# power.net
KiCad netlist of a schematic drawn in Altium Designer
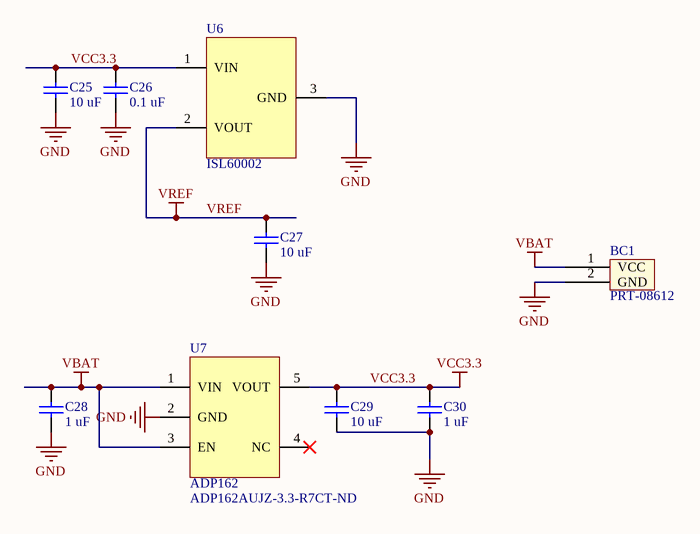
[diagram p0: power.SchDoc]

(export (version "E")
  (design (tool "Eeschema 10.0.6"))
  (components
    (comp (ref "BC1")
      (value "PRT-08612")
      (footprint "JST PH 2PIN")
      (description "2-pin JST-PH 2mm Battery Connector")
      (libsource (lib "opo_general") (part "JST-PH-2mm-2Pin"))
    )
    (comp (ref "C25")
      (value "10 uF")
      (footprint "0603")
      (description "Ceramic capacitor, 10 uF, 0603 package")
      (fields (field (name "TOLERANCE") "20%") (field (name "Comment") "Ceramic capacitor"))
      (libsource (lib "rlc") (part "C_10u_0603_ceramic"))
    )
    (comp (ref "C26")
      (value "0.1 uF")
      (footprint "0402")
      (description "Ceramic capacitor, 0.1u, 0402 package")
      (fields (field (name "TOLERANCE") "10%") (field (name "Comment") "Ceramic capacitor"))
      (libsource (lib "rlc") (part "C_0.1u_0402_ceramic"))
    )
    (comp (ref "C27")
      (value "10 uF")
      (footprint "0603")
      (description "Ceramic capacitor, 10 uF, 0603 package")
      (fields (field (name "TOLERANCE") "20%") (field (name "Comment") "Ceramic capacitor"))
      (libsource (lib "rlc") (part "C_10u_0603_ceramic"))
    )
    (comp (ref "C28")
      (value "1 uF")
      (footprint "0402")
      (description "Ceramic capacitor, 1 uF, 0402 package")
      (fields (field (name "TOLERANCE") "10%") (field (name "Comment") "Ceramic capacitor"))
      (libsource (lib "rlc") (part "C_1u_0402_ceramic"))
    )
    (comp (ref "C29")
      (value "10 uF")
      (footprint "0603")
      (description "Ceramic capacitor, 10 uF, 0603 package")
      (fields (field (name "TOLERANCE") "20%") (field (name "Comment") "Ceramic capacitor"))
      (libsource (lib "rlc") (part "C_10u_0603_ceramic"))
    )
    (comp (ref "C30")
      (value "1 uF")
      (footprint "0402")
      (description "Ceramic capacitor, 1 uF, 0402 package")
      (fields (field (name "TOLERANCE") "10%") (field (name "Comment") "Ceramic capacitor"))
      (libsource (lib "rlc") (part "C_1u_0402_ceramic"))
    )
    (comp (ref "U6")
      (value "ISL60002")
      (footprint "SOT23-3N")
      (description "IC VREF SERIES PREC SOT-23-3")
      (libsource (lib "opo") (part "ISL60002"))
    )
    (comp (ref "U7")
      (value "ADP162")
      (footprint "TSOT23-5")
      (description "Ultralow Quiescent Current,  150 mA, CMOS Linear Regulators")
      (fields (field (name "SUPPLIER PART NUMBER 1") "ADP162AUJZ-3.3-R7CT-ND"))
      (libsource (lib "opo") (part "ADP162"))
    )
  )
  (nets
    (net (code "1") (name "GND") (class "Default")
      (node (ref "BC1") (pin "2") (pinfunction "GND_2") (pintype "passive"))
      (node (ref "C25") (pin "2") (pintype "passive"))
      (node (ref "C26") (pin "2") (pintype "passive"))
      (node (ref "C27") (pin "2") (pintype "passive"))
      (node (ref "C28") (pin "2") (pintype "passive"))
      (node (ref "C29") (pin "2") (pintype "passive"))
      (node (ref "C30") (pin "2") (pintype "passive"))
      (node (ref "U6") (pin "3") (pinfunction "GND_3") (pintype "passive"))
      (node (ref "U7") (pin "2") (pinfunction "GND_2") (pintype "passive"))
    )
    (net (code "2") (name "VBAT") (class "Default")
      (node (ref "BC1") (pin "1") (pinfunction "VCC_1") (pintype "passive"))
      (node (ref "C28") (pin "1") (pintype "passive"))
      (node (ref "U7") (pin "1") (pinfunction "VIN_1") (pintype "passive"))
      (node (ref "U7") (pin "3") (pinfunction "EN_3") (pintype "passive"))
    )
    (net (code "3") (name "VCC3.3") (class "Default")
      (node (ref "C25") (pin "1") (pintype "passive"))
      (node (ref "C26") (pin "1") (pintype "passive"))
      (node (ref "C29") (pin "1") (pintype "passive"))
      (node (ref "C30") (pin "1") (pintype "passive"))
      (node (ref "U6") (pin "1") (pinfunction "VIN_1") (pintype "passive"))
      (node (ref "U7") (pin "5") (pinfunction "VOUT_5") (pintype "passive"))
    )
    (net (code "4") (name "VREF") (class "Default")
      (node (ref "C27") (pin "1") (pintype "passive"))
      (node (ref "U6") (pin "2") (pinfunction "VOUT_2") (pintype "passive"))
    )
    (net (code "5") (name "unconnected-(BC1-Pad3)") (class "Default")
      (node (ref "BC1") (pin "3") (pinfunction "3_3") (pintype "passive"))
    )
    (net (code "6") (name "unconnected-(BC1-Pad4)") (class "Default")
      (node (ref "BC1") (pin "4") (pinfunction "4_4") (pintype "passive"))
    )
    (net (code "7") (name "unconnected-(U7-NC-Pad4)") (class "Default")
      (node (ref "U7") (pin "4") (pinfunction "NC_4") (pintype "passive+no_connect"))
    )
  )
)
